# d150_zm1000_socket_rev_a.net
KiCad netlist of a schematic drawn in EAGLE
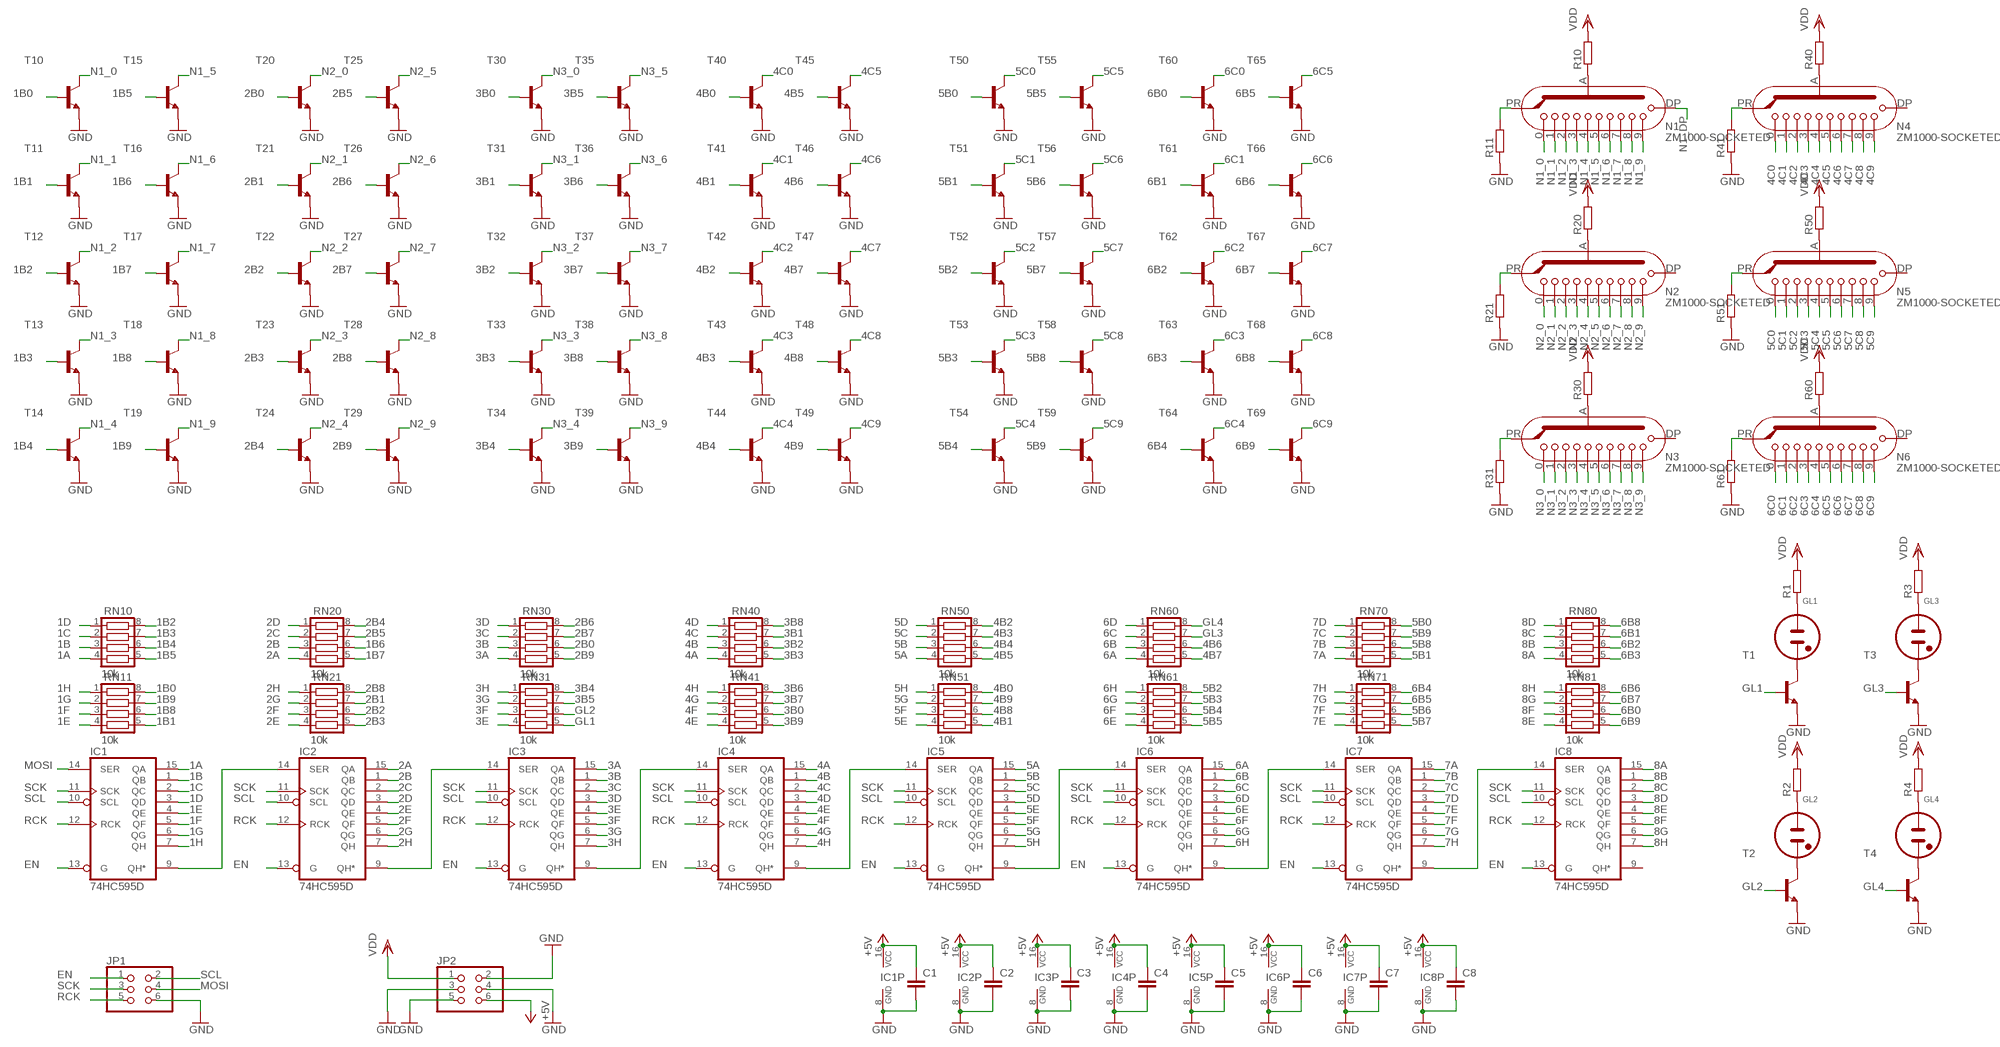
[diagram p0: schematic, sheet 1]

(export (version "E")
  (design (tool "Eeschema 10.0.6"))
  (components
    (comp (ref "C1")
      (value "C-EUC0603")
      (footprint "eagle-import:C0603")
      (libsource (lib "eagle-import") (part "C-EUC0603"))
    )
    (comp (ref "C2")
      (value "C-EUC0603")
      (footprint "eagle-import:C0603")
      (libsource (lib "eagle-import") (part "C-EUC0603"))
    )
    (comp (ref "C3")
      (value "C-EUC0603")
      (footprint "eagle-import:C0603")
      (libsource (lib "eagle-import") (part "C-EUC0603"))
    )
    (comp (ref "C4")
      (value "C-EUC0603")
      (footprint "eagle-import:C0603")
      (libsource (lib "eagle-import") (part "C-EUC0603"))
    )
    (comp (ref "C5")
      (value "C-EUC0603")
      (footprint "eagle-import:C0603")
      (libsource (lib "eagle-import") (part "C-EUC0603"))
    )
    (comp (ref "C6")
      (value "C-EUC0603")
      (footprint "eagle-import:C0603")
      (libsource (lib "eagle-import") (part "C-EUC0603"))
    )
    (comp (ref "C7")
      (value "C-EUC0603")
      (footprint "eagle-import:C0603")
      (libsource (lib "eagle-import") (part "C-EUC0603"))
    )
    (comp (ref "C8")
      (value "C-EUC0603")
      (footprint "eagle-import:C0603")
      (libsource (lib "eagle-import") (part "C-EUC0603"))
    )
    (comp (ref "GL1")
      (value "NE2-NEON-BULB-DRILL")
      (footprint "eagle-import:NE2-NEON-BULB-DRILL")
      (libsource (lib "eagle-import") (part "NE2-NEON-BULB-DRILL"))
    )
    (comp (ref "GL2")
      (value "NE2-NEON-BULB-DRILL")
      (footprint "eagle-import:NE2-NEON-BULB-DRILL")
      (libsource (lib "eagle-import") (part "NE2-NEON-BULB-DRILL"))
    )
    (comp (ref "GL3")
      (value "NE2-NEON-BULB-DRILL")
      (footprint "eagle-import:NE2-NEON-BULB-DRILL")
      (libsource (lib "eagle-import") (part "NE2-NEON-BULB-DRILL"))
    )
    (comp (ref "GL4")
      (value "NE2-NEON-BULB-DRILL")
      (footprint "eagle-import:NE2-NEON-BULB-DRILL")
      (libsource (lib "eagle-import") (part "NE2-NEON-BULB-DRILL"))
    )
    (comp (ref "IC1")
      (value "74HC595D")
      (footprint "eagle-import:SO16")
      (libsource (lib "eagle-import") (part "74595DHC"))
    )
    (comp (ref "IC2")
      (value "74HC595D")
      (footprint "eagle-import:SO16")
      (libsource (lib "eagle-import") (part "74595DHC"))
    )
    (comp (ref "IC3")
      (value "74HC595D")
      (footprint "eagle-import:SO16")
      (libsource (lib "eagle-import") (part "74595DHC"))
    )
    (comp (ref "IC4")
      (value "74HC595D")
      (footprint "eagle-import:SO16")
      (libsource (lib "eagle-import") (part "74595DHC"))
    )
    (comp (ref "IC5")
      (value "74HC595D")
      (footprint "eagle-import:SO16")
      (libsource (lib "eagle-import") (part "74595DHC"))
    )
    (comp (ref "IC6")
      (value "74HC595D")
      (footprint "eagle-import:SO16")
      (libsource (lib "eagle-import") (part "74595DHC"))
    )
    (comp (ref "IC7")
      (value "74HC595D")
      (footprint "eagle-import:SO16")
      (libsource (lib "eagle-import") (part "74595DHC"))
    )
    (comp (ref "IC8")
      (value "74HC595D")
      (footprint "eagle-import:SO16")
      (libsource (lib "eagle-import") (part "74595DHC"))
    )
    (comp (ref "JP1")
      (value "PINHD-2X3_2.54-SMD")
      (footprint "eagle-import:2X03SMD")
      (libsource (lib "eagle-import") (part "PINHD-2X3_2.54-SMD"))
    )
    (comp (ref "JP2")
      (value "PINHD-2X3_2.54-SMD")
      (footprint "eagle-import:2X03SMD")
      (libsource (lib "eagle-import") (part "PINHD-2X3_2.54-SMD"))
    )
    (comp (ref "N1")
      (value "ZM1000-SOCKETED")
      (footprint "eagle-import:ZM1000-SOCKETED")
      (libsource (lib "eagle-import") (part "ZM1000-SOCKETED"))
    )
    (comp (ref "N2")
      (value "ZM1000-SOCKETED")
      (footprint "eagle-import:ZM1000-SOCKETED")
      (libsource (lib "eagle-import") (part "ZM1000-SOCKETED"))
    )
    (comp (ref "N3")
      (value "ZM1000-SOCKETED")
      (footprint "eagle-import:ZM1000-SOCKETED")
      (libsource (lib "eagle-import") (part "ZM1000-SOCKETED"))
    )
    (comp (ref "N4")
      (value "ZM1000-SOCKETED")
      (footprint "eagle-import:ZM1000-SOCKETED")
      (libsource (lib "eagle-import") (part "ZM1000-SOCKETED"))
    )
    (comp (ref "N5")
      (value "ZM1000-SOCKETED")
      (footprint "eagle-import:ZM1000-SOCKETED")
      (libsource (lib "eagle-import") (part "ZM1000-SOCKETED"))
    )
    (comp (ref "N6")
      (value "ZM1000-SOCKETED")
      (footprint "eagle-import:ZM1000-SOCKETED")
      (libsource (lib "eagle-import") (part "ZM1000-SOCKETED"))
    )
    (comp (ref "R1")
      (value "R-EU_R0603")
      (footprint "eagle-import:R0603")
      (libsource (lib "eagle-import") (part "R-EU_R0603"))
    )
    (comp (ref "R2")
      (value "R-EU_R0603")
      (footprint "eagle-import:R0603")
      (libsource (lib "eagle-import") (part "R-EU_R0603"))
    )
    (comp (ref "R3")
      (value "R-EU_R0603")
      (footprint "eagle-import:R0603")
      (libsource (lib "eagle-import") (part "R-EU_R0603"))
    )
    (comp (ref "R4")
      (value "R-EU_R0603")
      (footprint "eagle-import:R0603")
      (libsource (lib "eagle-import") (part "R-EU_R0603"))
    )
    (comp (ref "R10")
      (value "R-EU_R0603")
      (footprint "eagle-import:R0603")
      (libsource (lib "eagle-import") (part "R-EU_R0603"))
    )
    (comp (ref "R11")
      (value "R-EU_R0603")
      (footprint "eagle-import:R0603")
      (libsource (lib "eagle-import") (part "R-EU_R0603"))
    )
    (comp (ref "R20")
      (value "R-EU_R0603")
      (footprint "eagle-import:R0603")
      (libsource (lib "eagle-import") (part "R-EU_R0603"))
    )
    (comp (ref "R21")
      (value "R-EU_R0603")
      (footprint "eagle-import:R0603")
      (libsource (lib "eagle-import") (part "R-EU_R0603"))
    )
    (comp (ref "R30")
      (value "R-EU_R0603")
      (footprint "eagle-import:R0603")
      (libsource (lib "eagle-import") (part "R-EU_R0603"))
    )
    (comp (ref "R31")
      (value "R-EU_R0603")
      (footprint "eagle-import:R0603")
      (libsource (lib "eagle-import") (part "R-EU_R0603"))
    )
    (comp (ref "R40")
      (value "R-EU_R0603")
      (footprint "eagle-import:R0603")
      (libsource (lib "eagle-import") (part "R-EU_R0603"))
    )
    (comp (ref "R41")
      (value "R-EU_R0603")
      (footprint "eagle-import:R0603")
      (libsource (lib "eagle-import") (part "R-EU_R0603"))
    )
    (comp (ref "R50")
      (value "R-EU_R0603")
      (footprint "eagle-import:R0603")
      (libsource (lib "eagle-import") (part "R-EU_R0603"))
    )
    (comp (ref "R51")
      (value "R-EU_R0603")
      (footprint "eagle-import:R0603")
      (libsource (lib "eagle-import") (part "R-EU_R0603"))
    )
    (comp (ref "R60")
      (value "R-EU_R0603")
      (footprint "eagle-import:R0603")
      (libsource (lib "eagle-import") (part "R-EU_R0603"))
    )
    (comp (ref "R61")
      (value "R-EU_R0603")
      (footprint "eagle-import:R0603")
      (libsource (lib "eagle-import") (part "R-EU_R0603"))
    )
    (comp (ref "RN10")
      (value "10k")
      (footprint "eagle-import:CTS742C083")
      (fields (field (name "OC_FARNELL") "unknown") (field (name "OC_NEWARK") "unknown"))
      (libsource (lib "eagle-import") (part "CTS742C083"))
    )
    (comp (ref "RN11")
      (value "10k")
      (footprint "eagle-import:CTS742C083")
      (fields (field (name "OC_FARNELL") "unknown") (field (name "OC_NEWARK") "unknown"))
      (libsource (lib "eagle-import") (part "CTS742C083"))
    )
    (comp (ref "RN20")
      (value "10k")
      (footprint "eagle-import:CTS742C083")
      (fields (field (name "OC_FARNELL") "unknown") (field (name "OC_NEWARK") "unknown"))
      (libsource (lib "eagle-import") (part "CTS742C083"))
    )
    (comp (ref "RN21")
      (value "10k")
      (footprint "eagle-import:CTS742C083")
      (fields (field (name "OC_FARNELL") "unknown") (field (name "OC_NEWARK") "unknown"))
      (libsource (lib "eagle-import") (part "CTS742C083"))
    )
    (comp (ref "RN30")
      (value "10k")
      (footprint "eagle-import:CTS742C083")
      (fields (field (name "OC_FARNELL") "unknown") (field (name "OC_NEWARK") "unknown"))
      (libsource (lib "eagle-import") (part "CTS742C083"))
    )
    (comp (ref "RN31")
      (value "10k")
      (footprint "eagle-import:CTS742C083")
      (fields (field (name "OC_FARNELL") "unknown") (field (name "OC_NEWARK") "unknown"))
      (libsource (lib "eagle-import") (part "CTS742C083"))
    )
    (comp (ref "RN40")
      (value "10k")
      (footprint "eagle-import:CTS742C083")
      (fields (field (name "OC_FARNELL") "unknown") (field (name "OC_NEWARK") "unknown"))
      (libsource (lib "eagle-import") (part "CTS742C083"))
    )
    (comp (ref "RN41")
      (value "10k")
      (footprint "eagle-import:CTS742C083")
      (fields (field (name "OC_FARNELL") "unknown") (field (name "OC_NEWARK") "unknown"))
      (libsource (lib "eagle-import") (part "CTS742C083"))
    )
    (comp (ref "RN50")
      (value "10k")
      (footprint "eagle-import:CTS742C083")
      (fields (field (name "OC_FARNELL") "unknown") (field (name "OC_NEWARK") "unknown"))
      (libsource (lib "eagle-import") (part "CTS742C083"))
    )
    (comp (ref "RN51")
      (value "10k")
      (footprint "eagle-import:CTS742C083")
      (fields (field (name "OC_FARNELL") "unknown") (field (name "OC_NEWARK") "unknown"))
      (libsource (lib "eagle-import") (part "CTS742C083"))
    )
    (comp (ref "RN60")
      (value "10k")
      (footprint "eagle-import:CTS742C083")
      (fields (field (name "OC_FARNELL") "unknown") (field (name "OC_NEWARK") "unknown"))
      (libsource (lib "eagle-import") (part "CTS742C083"))
    )
    (comp (ref "RN61")
      (value "10k")
      (footprint "eagle-import:CTS742C083")
      (fields (field (name "OC_FARNELL") "unknown") (field (name "OC_NEWARK") "unknown"))
      (libsource (lib "eagle-import") (part "CTS742C083"))
    )
    (comp (ref "RN70")
      (value "10k")
      (footprint "eagle-import:CTS742C083")
      (fields (field (name "OC_FARNELL") "unknown") (field (name "OC_NEWARK") "unknown"))
      (libsource (lib "eagle-import") (part "CTS742C083"))
    )
    (comp (ref "RN71")
      (value "10k")
      (footprint "eagle-import:CTS742C083")
      (fields (field (name "OC_FARNELL") "unknown") (field (name "OC_NEWARK") "unknown"))
      (libsource (lib "eagle-import") (part "CTS742C083"))
    )
    (comp (ref "RN80")
      (value "10k")
      (footprint "eagle-import:CTS742C083")
      (fields (field (name "OC_FARNELL") "unknown") (field (name "OC_NEWARK") "unknown"))
      (libsource (lib "eagle-import") (part "CTS742C083"))
    )
    (comp (ref "RN81")
      (value "10k")
      (footprint "eagle-import:CTS742C083")
      (fields (field (name "OC_FARNELL") "unknown") (field (name "OC_NEWARK") "unknown"))
      (libsource (lib "eagle-import") (part "CTS742C083"))
    )
    (comp (ref "T1")
      (value "SMBTA42")
      (footprint "eagle-import:SOT23")
      (libsource (lib "eagle-import") (part "SMBTA42"))
    )
    (comp (ref "T2")
      (value "SMBTA42")
      (footprint "eagle-import:SOT23")
      (libsource (lib "eagle-import") (part "SMBTA42"))
    )
    (comp (ref "T3")
      (value "SMBTA42")
      (footprint "eagle-import:SOT23")
      (libsource (lib "eagle-import") (part "SMBTA42"))
    )
    (comp (ref "T4")
      (value "SMBTA42")
      (footprint "eagle-import:SOT23")
      (libsource (lib "eagle-import") (part "SMBTA42"))
    )
    (comp (ref "T10")
      (value "SMBTA42")
      (footprint "eagle-import:SOT23")
      (libsource (lib "eagle-import") (part "SMBTA42"))
    )
    (comp (ref "T11")
      (value "SMBTA42")
      (footprint "eagle-import:SOT23")
      (libsource (lib "eagle-import") (part "SMBTA42"))
    )
    (comp (ref "T12")
      (value "SMBTA42")
      (footprint "eagle-import:SOT23")
      (libsource (lib "eagle-import") (part "SMBTA42"))
    )
    (comp (ref "T13")
      (value "SMBTA42")
      (footprint "eagle-import:SOT23")
      (libsource (lib "eagle-import") (part "SMBTA42"))
    )
    (comp (ref "T14")
      (value "SMBTA42")
      (footprint "eagle-import:SOT23")
      (libsource (lib "eagle-import") (part "SMBTA42"))
    )
    (comp (ref "T15")
      (value "SMBTA42")
      (footprint "eagle-import:SOT23")
      (libsource (lib "eagle-import") (part "SMBTA42"))
    )
    (comp (ref "T16")
      (value "SMBTA42")
      (footprint "eagle-import:SOT23")
      (libsource (lib "eagle-import") (part "SMBTA42"))
    )
    (comp (ref "T17")
      (value "SMBTA42")
      (footprint "eagle-import:SOT23")
      (libsource (lib "eagle-import") (part "SMBTA42"))
    )
    (comp (ref "T18")
      (value "SMBTA42")
      (footprint "eagle-import:SOT23")
      (libsource (lib "eagle-import") (part "SMBTA42"))
    )
    (comp (ref "T19")
      (value "SMBTA42")
      (footprint "eagle-import:SOT23")
      (libsource (lib "eagle-import") (part "SMBTA42"))
    )
    (comp (ref "T20")
      (value "SMBTA42")
      (footprint "eagle-import:SOT23")
      (libsource (lib "eagle-import") (part "SMBTA42"))
    )
    (comp (ref "T21")
      (value "SMBTA42")
      (footprint "eagle-import:SOT23")
      (libsource (lib "eagle-import") (part "SMBTA42"))
    )
    (comp (ref "T22")
      (value "SMBTA42")
      (footprint "eagle-import:SOT23")
      (libsource (lib "eagle-import") (part "SMBTA42"))
    )
    (comp (ref "T23")
      (value "SMBTA42")
      (footprint "eagle-import:SOT23")
      (libsource (lib "eagle-import") (part "SMBTA42"))
    )
    (comp (ref "T24")
      (value "SMBTA42")
      (footprint "eagle-import:SOT23")
      (libsource (lib "eagle-import") (part "SMBTA42"))
    )
    (comp (ref "T25")
      (value "SMBTA42")
      (footprint "eagle-import:SOT23")
      (libsource (lib "eagle-import") (part "SMBTA42"))
    )
    (comp (ref "T26")
      (value "SMBTA42")
      (footprint "eagle-import:SOT23")
      (libsource (lib "eagle-import") (part "SMBTA42"))
    )
    (comp (ref "T27")
      (value "SMBTA42")
      (footprint "eagle-import:SOT23")
      (libsource (lib "eagle-import") (part "SMBTA42"))
    )
    (comp (ref "T28")
      (value "SMBTA42")
      (footprint "eagle-import:SOT23")
      (libsource (lib "eagle-import") (part "SMBTA42"))
    )
    (comp (ref "T29")
      (value "SMBTA42")
      (footprint "eagle-import:SOT23")
      (libsource (lib "eagle-import") (part "SMBTA42"))
    )
    (comp (ref "T30")
      (value "SMBTA42")
      (footprint "eagle-import:SOT23")
      (libsource (lib "eagle-import") (part "SMBTA42"))
    )
    (comp (ref "T31")
      (value "SMBTA42")
      (footprint "eagle-import:SOT23")
      (libsource (lib "eagle-import") (part "SMBTA42"))
    )
    (comp (ref "T32")
      (value "SMBTA42")
      (footprint "eagle-import:SOT23")
      (libsource (lib "eagle-import") (part "SMBTA42"))
    )
    (comp (ref "T33")
      (value "SMBTA42")
      (footprint "eagle-import:SOT23")
      (libsource (lib "eagle-import") (part "SMBTA42"))
    )
    (comp (ref "T34")
      (value "SMBTA42")
      (footprint "eagle-import:SOT23")
      (libsource (lib "eagle-import") (part "SMBTA42"))
    )
    (comp (ref "T35")
      (value "SMBTA42")
      (footprint "eagle-import:SOT23")
      (libsource (lib "eagle-import") (part "SMBTA42"))
    )
    (comp (ref "T36")
      (value "SMBTA42")
      (footprint "eagle-import:SOT23")
      (libsource (lib "eagle-import") (part "SMBTA42"))
    )
    (comp (ref "T37")
      (value "SMBTA42")
      (footprint "eagle-import:SOT23")
      (libsource (lib "eagle-import") (part "SMBTA42"))
    )
    (comp (ref "T38")
      (value "SMBTA42")
      (footprint "eagle-import:SOT23")
      (libsource (lib "eagle-import") (part "SMBTA42"))
    )
    (comp (ref "T39")
      (value "SMBTA42")
      (footprint "eagle-import:SOT23")
      (libsource (lib "eagle-import") (part "SMBTA42"))
    )
    (comp (ref "T40")
      (value "SMBTA42")
      (footprint "eagle-import:SOT23")
      (libsource (lib "eagle-import") (part "SMBTA42"))
    )
    (comp (ref "T41")
      (value "SMBTA42")
      (footprint "eagle-import:SOT23")
      (libsource (lib "eagle-import") (part "SMBTA42"))
    )
    (comp (ref "T42")
      (value "SMBTA42")
      (footprint "eagle-import:SOT23")
      (libsource (lib "eagle-import") (part "SMBTA42"))
    )
    (comp (ref "T43")
      (value "SMBTA42")
      (footprint "eagle-import:SOT23")
      (libsource (lib "eagle-import") (part "SMBTA42"))
    )
    (comp (ref "T44")
      (value "SMBTA42")
      (footprint "eagle-import:SOT23")
      (libsource (lib "eagle-import") (part "SMBTA42"))
    )
    (comp (ref "T45")
      (value "SMBTA42")
      (footprint "eagle-import:SOT23")
      (libsource (lib "eagle-import") (part "SMBTA42"))
    )
    (comp (ref "T46")
      (value "SMBTA42")
      (footprint "eagle-import:SOT23")
      (libsource (lib "eagle-import") (part "SMBTA42"))
    )
    (comp (ref "T47")
      (value "SMBTA42")
      (footprint "eagle-import:SOT23")
      (libsource (lib "eagle-import") (part "SMBTA42"))
    )
    (comp (ref "T48")
      (value "SMBTA42")
      (footprint "eagle-import:SOT23")
      (libsource (lib "eagle-import") (part "SMBTA42"))
    )
    (comp (ref "T49")
      (value "SMBTA42")
      (footprint "eagle-import:SOT23")
      (libsource (lib "eagle-import") (part "SMBTA42"))
    )
    (comp (ref "T50")
      (value "SMBTA42")
      (footprint "eagle-import:SOT23")
      (libsource (lib "eagle-import") (part "SMBTA42"))
    )
    (comp (ref "T51")
      (value "SMBTA42")
      (footprint "eagle-import:SOT23")
      (libsource (lib "eagle-import") (part "SMBTA42"))
    )
    (comp (ref "T52")
      (value "SMBTA42")
      (footprint "eagle-import:SOT23")
      (libsource (lib "eagle-import") (part "SMBTA42"))
    )
    (comp (ref "T53")
      (value "SMBTA42")
      (footprint "eagle-import:SOT23")
      (libsource (lib "eagle-import") (part "SMBTA42"))
    )
    (comp (ref "T54")
      (value "SMBTA42")
      (footprint "eagle-import:SOT23")
      (libsource (lib "eagle-import") (part "SMBTA42"))
    )
    (comp (ref "T55")
      (value "SMBTA42")
      (footprint "eagle-import:SOT23")
      (libsource (lib "eagle-import") (part "SMBTA42"))
    )
    (comp (ref "T56")
      (value "SMBTA42")
      (footprint "eagle-import:SOT23")
      (libsource (lib "eagle-import") (part "SMBTA42"))
    )
    (comp (ref "T57")
      (value "SMBTA42")
      (footprint "eagle-import:SOT23")
      (libsource (lib "eagle-import") (part "SMBTA42"))
    )
    (comp (ref "T58")
      (value "SMBTA42")
      (footprint "eagle-import:SOT23")
      (libsource (lib "eagle-import") (part "SMBTA42"))
    )
    (comp (ref "T59")
      (value "SMBTA42")
      (footprint "eagle-import:SOT23")
      (libsource (lib "eagle-import") (part "SMBTA42"))
    )
    (comp (ref "T60")
      (value "SMBTA42")
      (footprint "eagle-import:SOT23")
      (libsource (lib "eagle-import") (part "SMBTA42"))
    )
    (comp (ref "T61")
      (value "SMBTA42")
      (footprint "eagle-import:SOT23")
      (libsource (lib "eagle-import") (part "SMBTA42"))
    )
    (comp (ref "T62")
      (value "SMBTA42")
      (footprint "eagle-import:SOT23")
      (libsource (lib "eagle-import") (part "SMBTA42"))
    )
    (comp (ref "T63")
      (value "SMBTA42")
      (footprint "eagle-import:SOT23")
      (libsource (lib "eagle-import") (part "SMBTA42"))
    )
    (comp (ref "T64")
      (value "SMBTA42")
      (footprint "eagle-import:SOT23")
      (libsource (lib "eagle-import") (part "SMBTA42"))
    )
    (comp (ref "T65")
      (value "SMBTA42")
      (footprint "eagle-import:SOT23")
      (libsource (lib "eagle-import") (part "SMBTA42"))
    )
    (comp (ref "T66")
      (value "SMBTA42")
      (footprint "eagle-import:SOT23")
      (libsource (lib "eagle-import") (part "SMBTA42"))
    )
    (comp (ref "T67")
      (value "SMBTA42")
      (footprint "eagle-import:SOT23")
      (libsource (lib "eagle-import") (part "SMBTA42"))
    )
    (comp (ref "T68")
      (value "SMBTA42")
      (footprint "eagle-import:SOT23")
      (libsource (lib "eagle-import") (part "SMBTA42"))
    )
    (comp (ref "T69")
      (value "SMBTA42")
      (footprint "eagle-import:SOT23")
      (libsource (lib "eagle-import") (part "SMBTA42"))
    )
  )
  (nets
    (net (code "1") (name "+5V") (class "Default")
      (node (ref "C1") (pin "1") (pinfunction "1_1") (pintype "passive"))
      (node (ref "C2") (pin "1") (pinfunction "1_1") (pintype "passive"))
      (node (ref "C3") (pin "1") (pinfunction "1_1") (pintype "passive"))
      (node (ref "C4") (pin "1") (pinfunction "1_1") (pintype "passive"))
      (node (ref "C5") (pin "1") (pinfunction "1_1") (pintype "passive"))
      (node (ref "C6") (pin "1") (pinfunction "1_1") (pintype "passive"))
      (node (ref "C7") (pin "1") (pinfunction "1_1") (pintype "passive"))
      (node (ref "C8") (pin "1") (pinfunction "1_1") (pintype "passive"))
      (node (ref "IC1") (pin "16") (pinfunction "VCC_16") (pintype "power_in"))
      (node (ref "IC2") (pin "16") (pinfunction "VCC_16") (pintype "power_in"))
      (node (ref "IC3") (pin "16") (pinfunction "VCC_16") (pintype "power_in"))
      (node (ref "IC4") (pin "16") (pinfunction "VCC_16") (pintype "power_in"))
      (node (ref "IC5") (pin "16") (pinfunction "VCC_16") (pintype "power_in"))
      (node (ref "IC6") (pin "16") (pinfunction "VCC_16") (pintype "power_in"))
      (node (ref "IC7") (pin "16") (pinfunction "VCC_16") (pintype "power_in"))
      (node (ref "IC8") (pin "16") (pinfunction "VCC_16") (pintype "power_in"))
      (node (ref "JP2") (pin "6") (pinfunction "6_6") (pintype "passive"))
    )
    (net (code "2") (name "/1A") (class "Default")
      (node (ref "IC1") (pin "15") (pinfunction "QA_15") (pintype "tri_state"))
      (node (ref "RN10") (pin "4") (pinfunction "4_4") (pintype "passive"))
    )
    (net (code "3") (name "/1B") (class "Default")
      (node (ref "IC1") (pin "1") (pinfunction "QB_1") (pintype "tri_state"))
      (node (ref "RN10") (pin "3") (pinfunction "3_3") (pintype "passive"))
    )
    (net (code "4") (name "/1B0") (class "Default")
      (node (ref "RN11") (pin "8") (pinfunction "8_8") (pintype "passive"))
      (node (ref "T10") (pin "1") (pinfunction "B_1") (pintype "passive"))
    )
    (net (code "5") (name "/1B1") (class "Default")
      (node (ref "RN11") (pin "5") (pinfunction "5_5") (pintype "passive"))
      (node (ref "T11") (pin "1") (pinfunction "B_1") (pintype "passive"))
    )
    (net (code "6") (name "/1B2") (class "Default")
      (node (ref "RN10") (pin "8") (pinfunction "8_8") (pintype "passive"))
      (node (ref "T12") (pin "1") (pinfunction "B_1") (pintype "passive"))
    )
    (net (code "7") (name "/1B3") (class "Default")
      (node (ref "RN10") (pin "7") (pinfunction "7_7") (pintype "passive"))
      (node (ref "T13") (pin "1") (pinfunction "B_1") (pintype "passive"))
    )
    (net (code "8") (name "/1B4") (class "Default")
      (node (ref "RN10") (pin "6") (pinfunction "6_6") (pintype "passive"))
      (node (ref "T14") (pin "1") (pinfunction "B_1") (pintype "passive"))
    )
    (net (code "9") (name "/1B5") (class "Default")
      (node (ref "RN10") (pin "5") (pinfunction "5_5") (pintype "passive"))
      (node (ref "T15") (pin "1") (pinfunction "B_1") (pintype "passive"))
    )
    (net (code "10") (name "/1B6") (class "Default")
      (node (ref "RN20") (pin "6") (pinfunction "6_6") (pintype "passive"))
      (node (ref "T16") (pin "1") (pinfunction "B_1") (pintype "passive"))
    )
    (net (code "11") (name "/1B7") (class "Default")
      (node (ref "RN20") (pin "5") (pinfunction "5_5") (pintype "passive"))
      (node (ref "T17") (pin "1") (pinfunction "B_1") (pintype "passive"))
    )
    (net (code "12") (name "/1B8") (class "Default")
      (node (ref "RN11") (pin "6") (pinfunction "6_6") (pintype "passive"))
      (node (ref "T18") (pin "1") (pinfunction "B_1") (pintype "passive"))
    )
    (net (code "13") (name "/1B9") (class "Default")
      (node (ref "RN11") (pin "7") (pinfunction "7_7") (pintype "passive"))
      (node (ref "T19") (pin "1") (pinfunction "B_1") (pintype "passive"))
    )
    (net (code "14") (name "/1C") (class "Default")
      (node (ref "IC1") (pin "2") (pinfunction "QC_2") (pintype "tri_state"))
      (node (ref "RN10") (pin "2") (pinfunction "2_2") (pintype "passive"))
    )
    (net (code "15") (name "/1D") (class "Default")
      (node (ref "IC1") (pin "3") (pinfunction "QD_3") (pintype "tri_state"))
      (node (ref "RN10") (pin "1") (pinfunction "1_1") (pintype "passive"))
    )
    (net (code "16") (name "/1E") (class "Default")
      (node (ref "IC1") (pin "4") (pinfunction "QE_4") (pintype "tri_state"))
      (node (ref "RN11") (pin "4") (pinfunction "4_4") (pintype "passive"))
    )
    (net (code "17") (name "/1F") (class "Default")
      (node (ref "IC1") (pin "5") (pinfunction "QF_5") (pintype "tri_state"))
      (node (ref "RN11") (pin "3") (pinfunction "3_3") (pintype "passive"))
    )
    (net (code "18") (name "/1G") (class "Default")
      (node (ref "IC1") (pin "6") (pinfunction "QG_6") (pintype "tri_state"))
      (node (ref "RN11") (pin "2") (pinfunction "2_2") (pintype "passive"))
    )
    (net (code "19") (name "/1H") (class "Default")
      (node (ref "IC1") (pin "7") (pinfunction "QH_7") (pintype "tri_state"))
      (node (ref "RN11") (pin "1") (pinfunction "1_1") (pintype "passive"))
    )
    (net (code "20") (name "/2A") (class "Default")
      (node (ref "IC2") (pin "15") (pinfunction "QA_15") (pintype "tri_state"))
      (node (ref "RN20") (pin "4") (pinfunction "4_4") (pintype "passive"))
    )
    (net (code "21") (name "/2B") (class "Default")
      (node (ref "IC2") (pin "1") (pinfunction "QB_1") (pintype "tri_state"))
      (node (ref "RN20") (pin "3") (pinfunction "3_3") (pintype "passive"))
    )
    (net (code "22") (name "/2B0") (class "Default")
      (node (ref "RN30") (pin "6") (pinfunction "6_6") (pintype "passive"))
      (node (ref "T20") (pin "1") (pinfunction "B_1") (pintype "passive"))
    )
    (net (code "23") (name "/2B1") (class "Default")
      (node (ref "RN21") (pin "7") (pinfunction "7_7") (pintype "passive"))
      (node (ref "T21") (pin "1") (pinfunction "B_1") (pintype "passive"))
    )
    (net (code "24") (name "/2B2") (class "Default")
      (node (ref "RN21") (pin "6") (pinfunction "6_6") (pintype "passive"))
      (node (ref "T22") (pin "1") (pinfunction "B_1") (pintype "passive"))
    )
    (net (code "25") (name "/2B3") (class "Default")
      (node (ref "RN21") (pin "5") (pinfunction "5_5") (pintype "passive"))
      (node (ref "T23") (pin "1") (pinfunction "B_1") (pintype "passive"))
    )
    (net (code "26") (name "/2B4") (class "Default")
      (node (ref "RN20") (pin "8") (pinfunction "8_8") (pintype "passive"))
      (node (ref "T24") (pin "1") (pinfunction "B_1") (pintype "passive"))
    )
    (net (code "27") (name "/2B5") (class "Default")
      (node (ref "RN20") (pin "7") (pinfunction "7_7") (pintype "passive"))
      (node (ref "T25") (pin "1") (pinfunction "B_1") (pintype "passive"))
    )
    (net (code "28") (name "/2B6") (class "Default")
      (node (ref "RN30") (pin "8") (pinfunction "8_8") (pintype "passive"))
      (node (ref "T26") (pin "1") (pinfunction "B_1") (pintype "passive"))
    )
    (net (code "29") (name "/2B7") (class "Default")
      (node (ref "RN30") (pin "7") (pinfunction "7_7") (pintype "passive"))
      (node (ref "T27") (pin "1") (pinfunction "B_1") (pintype "passive"))
    )
    (net (code "30") (name "/2B8") (class "Default")
      (node (ref "RN21") (pin "8") (pinfunction "8_8") (pintype "passive"))
      (node (ref "T28") (pin "1") (pinfunction "B_1") (pintype "passive"))
    )
    (net (code "31") (name "/2B9") (class "Default")
      (node (ref "RN30") (pin "5") (pinfunction "5_5") (pintype "passive"))
      (node (ref "T29") (pin "1") (pinfunction "B_1") (pintype "passive"))
    )
    (net (code "32") (name "/2C") (class "Default")
      (node (ref "IC2") (pin "2") (pinfunction "QC_2") (pintype "tri_state"))
      (node (ref "RN20") (pin "2") (pinfunction "2_2") (pintype "passive"))
    )
    (net (code "33") (name "/2D") (class "Default")
      (node (ref "IC2") (pin "3") (pinfunction "QD_3") (pintype "tri_state"))
      (node (ref "RN20") (pin "1") (pinfunction "1_1") (pintype "passive"))
    )
    (net (code "34") (name "/2E") (class "Default")
      (node (ref "IC2") (pin "4") (pinfunction "QE_4") (pintype "tri_state"))
      (node (ref "RN21") (pin "4") (pinfunction "4_4") (pintype "passive"))
    )
    (net (code "35") (name "/2F") (class "Default")
      (node (ref "IC2") (pin "5") (pinfunction "QF_5") (pintype "tri_state"))
      (node (ref "RN21") (pin "3") (pinfunction "3_3") (pintype "passive"))
    )
    (net (code "36") (name "/2G") (class "Default")
      (node (ref "IC2") (pin "6") (pinfunction "QG_6") (pintype "tri_state"))
      (node (ref "RN21") (pin "2") (pinfunction "2_2") (pintype "passive"))
    )
    (net (code "37") (name "/2H") (class "Default")
      (node (ref "IC2") (pin "7") (pinfunction "QH_7") (pintype "tri_state"))
      (node (ref "RN21") (pin "1") (pinfunction "1_1") (pintype "passive"))
    )
    (net (code "38") (name "/3A") (class "Default")
      (node (ref "IC3") (pin "15") (pinfunction "QA_15") (pintype "tri_state"))
      (node (ref "RN30") (pin "4") (pinfunction "4_4") (pintype "passive"))
    )
    (net (code "39") (name "/3B") (class "Default")
      (node (ref "IC3") (pin "1") (pinfunction "QB_1") (pintype "tri_state"))
      (node (ref "RN30") (pin "3") (pinfunction "3_3") (pintype "passive"))
    )
    (net (code "40") (name "/3B0") (class "Default")
      (node (ref "RN41") (pin "6") (pinfunction "6_6") (pintype "passive"))
      (node (ref "T30") (pin "1") (pinfunction "B_1") (pintype "passive"))
    )
    (net (code "41") (name "/3B1") (class "Default")
      (node (ref "RN40") (pin "7") (pinfunction "7_7") (pintype "passive"))
      (node (ref "T31") (pin "1") (pinfunction "B_1") (pintype "passive"))
    )
    (net (code "42") (name "/3B2") (class "Default")
      (node (ref "RN40") (pin "6") (pinfunction "6_6") (pintype "passive"))
      (node (ref "T32") (pin "1") (pinfunction "B_1") (pintype "passive"))
    )
    (net (code "43") (name "/3B3") (class "Default")
      (node (ref "RN40") (pin "5") (pinfunction "5_5") (pintype "passive"))
      (node (ref "T33") (pin "1") (pinfunction "B_1") (pintype "passive"))
    )
    (net (code "44") (name "/3B4") (class "Default")
      (node (ref "RN31") (pin "8") (pinfunction "8_8") (pintype "passive"))
      (node (ref "T34") (pin "1") (pinfunction "B_1") (pintype "passive"))
    )
    (net (code "45") (name "/3B5") (class "Default")
      (node (ref "RN31") (pin "7") (pinfunction "7_7") (pintype "passive"))
      (node (ref "T35") (pin "1") (pinfunction "B_1") (pintype "passive"))
    )
    (net (code "46") (name "/3B6") (class "Default")
      (node (ref "RN41") (pin "8") (pinfunction "8_8") (pintype "passive"))
      (node (ref "T36") (pin "1") (pinfunction "B_1") (pintype "passive"))
    )
    (net (code "47") (name "/3B7") (class "Default")
      (node (ref "RN41") (pin "7") (pinfunction "7_7") (pintype "passive"))
      (node (ref "T37") (pin "1") (pinfunction "B_1") (pintype "passive"))
    )
    (net (code "48") (name "/3B8") (class "Default")
      (node (ref "RN40") (pin "8") (pinfunction "8_8") (pintype "passive"))
      (node (ref "T38") (pin "1") (pinfunction "B_1") (pintype "passive"))
    )
    (net (code "49") (name "/3B9") (class "Default")
      (node (ref "RN41") (pin "5") (pinfunction "5_5") (pintype "passive"))
      (node (ref "T39") (pin "1") (pinfunction "B_1") (pintype "passive"))
    )
    (net (code "50") (name "/3C") (class "Default")
      (node (ref "IC3") (pin "2") (pinfunction "QC_2") (pintype "tri_state"))
      (node (ref "RN30") (pin "2") (pinfunction "2_2") (pintype "passive"))
    )
    (net (code "51") (name "/3D") (class "Default")
      (node (ref "IC3") (pin "3") (pinfunction "QD_3") (pintype "tri_state"))
      (node (ref "RN30") (pin "1") (pinfunction "1_1") (pintype "passive"))
    )
    (net (code "52") (name "/3E") (class "Default")
      (node (ref "IC3") (pin "4") (pinfunction "QE_4") (pintype "tri_state"))
      (node (ref "RN31") (pin "4") (pinfunction "4_4") (pintype "passive"))
    )
    (net (code "53") (name "/3F") (class "Default")
      (node (ref "IC3") (pin "5") (pinfunction "QF_5") (pintype "tri_state"))
      (node (ref "RN31") (pin "3") (pinfunction "3_3") (pintype "passive"))
    )
    (net (code "54") (name "/3G") (class "Default")
      (node (ref "IC3") (pin "6") (pinfunction "QG_6") (pintype "tri_state"))
      (node (ref "RN31") (pin "2") (pinfunction "2_2") (pintype "passive"))
    )
    (net (code "55") (name "/3H") (class "Default")
      (node (ref "IC3") (pin "7") (pinfunction "QH_7") (pintype "tri_state"))
      (node (ref "RN31") (pin "1") (pinfunction "1_1") (pintype "passive"))
    )
    (net (code "56") (name "/4A") (class "Default")
      (node (ref "IC4") (pin "15") (pinfunction "QA_15") (pintype "tri_state"))
      (node (ref "RN40") (pin "4") (pinfunction "4_4") (pintype "passive"))
    )
    (net (code "57") (name "/4B") (class "Default")
      (node (ref "IC4") (pin "1") (pinfunction "QB_1") (pintype "tri_state"))
      (node (ref "RN40") (pin "3") (pinfunction "3_3") (pintype "passive"))
    )
    (net (code "58") (name "/4B0") (class "Default")
      (node (ref "RN51") (pin "8") (pinfunction "8_8") (pintype "passive"))
      (node (ref "T40") (pin "1") (pinfunction "B_1") (pintype "passive"))
    )
    (net (code "59") (name "/4B1") (class "Default")
      (node (ref "RN51") (pin "5") (pinfunction "5_5") (pintype "passive"))
      (node (ref "T41") (pin "1") (pinfunction "B_1") (pintype "passive"))
    )
    (net (code "60") (name "/4B2") (class "Default")
      (node (ref "RN50") (pin "8") (pinfunction "8_8") (pintype "passive"))
      (node (ref "T42") (pin "1") (pinfunction "B_1") (pintype "passive"))
    )
    (net (code "61") (name "/4B3") (class "Default")
      (node (ref "RN50") (pin "7") (pinfunction "7_7") (pintype "passive"))
      (node (ref "T43") (pin "1") (pinfunction "B_1") (pintype "passive"))
    )
    (net (code "62") (name "/4B4") (class "Default")
      (node (ref "RN50") (pin "6") (pinfunction "6_6") (pintype "passive"))
      (node (ref "T44") (pin "1") (pinfunction "B_1") (pintype "passive"))
    )
    (net (code "63") (name "/4B5") (class "Default")
      (node (ref "RN50") (pin "5") (pinfunction "5_5") (pintype "passive"))
      (node (ref "T45") (pin "1") (pinfunction "B_1") (pintype "passive"))
    )
    (net (code "64") (name "/4B6") (class "Default")
      (node (ref "RN60") (pin "6") (pinfunction "6_6") (pintype "passive"))
      (node (ref "T46") (pin "1") (pinfunction "B_1") (pintype "passive"))
    )
    (net (code "65") (name "/4B7") (class "Default")
      (node (ref "RN60") (pin "5") (pinfunction "5_5") (pintype "passive"))
      (node (ref "T47") (pin "1") (pinfunction "B_1") (pintype "passive"))
    )
    (net (code "66") (name "/4B8") (class "Default")
      (node (ref "RN51") (pin "6") (pinfunction "6_6") (pintype "passive"))
      (node (ref "T48") (pin "1") (pinfunction "B_1") (pintype "passive"))
    )
    (net (code "67") (name "/4B9") (class "Default")
      (node (ref "RN51") (pin "7") (pinfunction "7_7") (pintype "passive"))
      (node (ref "T49") (pin "1") (pinfunction "B_1") (pintype "passive"))
    )
    (net (code "68") (name "/4C") (class "Default")
      (node (ref "IC4") (pin "2") (pinfunction "QC_2") (pintype "tri_state"))
      (node (ref "RN40") (pin "2") (pinfunction "2_2") (pintype "passive"))
    )
    (net (code "69") (name "/4C0") (class "Default")
      (node (ref "N4") (pin "K0") (pinfunction "0_K0") (pintype "bidirectional"))
      (node (ref "T40") (pin "3") (pinfunction "C_3") (pintype "passive"))
    )
    (net (code "70") (name "/4C1") (class "Default")
      (node (ref "N4") (pin "K1") (pinfunction "1_K1") (pintype "bidirectional"))
      (node (ref "T41") (pin "3") (pinfunction "C_3") (pintype "passive"))
    )
    (net (code "71") (name "/4C2") (class "Default")
      (node (ref "N4") (pin "K2") (pinfunction "2_K2") (pintype "bidirectional"))
      (node (ref "T42") (pin "3") (pinfunction "C_3") (pintype "passive"))
    )
    (net (code "72") (name "/4C3") (class "Default")
      (node (ref "N4") (pin "K3") (pinfunction "3_K3") (pintype "bidirectional"))
      (node (ref "T43") (pin "3") (pinfunction "C_3") (pintype "passive"))
    )
    (net (code "73") (name "/4C4") (class "Default")
      (node (ref "N4") (pin "K4") (pinfunction "4_K4") (pintype "bidirectional"))
      (node (ref "T44") (pin "3") (pinfunction "C_3") (pintype "passive"))
    )
    (net (code "74") (name "/4C5") (class "Default")
      (node (ref "N4") (pin "K5") (pinfunction "5_K5") (pintype "bidirectional"))
      (node (ref "T45") (pin "3") (pinfunction "C_3") (pintype "passive"))
    )
    (net (code "75") (name "/4C6") (class "Default")
      (node (ref "N4") (pin "K6") (pinfunction "6_K6") (pintype "bidirectional"))
      (node (ref "T46") (pin "3") (pinfunction "C_3") (pintype "passive"))
    )
    (net (code "76") (name "/4C7") (class "Default")
      (node (ref "N4") (pin "K7") (pinfunction "7_K7") (pintype "bidirectional"))
      (node (ref "T47") (pin "3") (pinfunction "C_3") (pintype "passive"))
    )
    (net (code "77") (name "/4C8") (class "Default")
      (node (ref "N4") (pin "K8") (pinfunction "8_K8") (pintype "bidirectional"))
      (node (ref "T48") (pin "3") (pinfunction "C_3") (pintype "passive"))
    )
    (net (code "78") (name "/4C9") (class "Default")
      (node (ref "N4") (pin "K9") (pinfunction "9_K9") (pintype "bidirectional"))
      (node (ref "T49") (pin "3") (pinfunction "C_3") (pintype "passive"))
    )
    (net (code "79") (name "/4D") (class "Default")
      (node (ref "IC4") (pin "3") (pinfunction "QD_3") (pintype "tri_state"))
      (node (ref "RN40") (pin "1") (pinfunction "1_1") (pintype "passive"))
    )
    (net (code "80") (name "/4E") (class "Default")
      (node (ref "IC4") (pin "4") (pinfunction "QE_4") (pintype "tri_state"))
      (node (ref "RN41") (pin "4") (pinfunction "4_4") (pintype "passive"))
    )
    (net (code "81") (name "/4F") (class "Default")
      (node (ref "IC4") (pin "5") (pinfunction "QF_5") (pintype "tri_state"))
      (node (ref "RN41") (pin "3") (pinfunction "3_3") (pintype "passive"))
    )
    (net (code "82") (name "/4G") (class "Default")
      (node (ref "IC4") (pin "6") (pinfunction "QG_6") (pintype "tri_state"))
      (node (ref "RN41") (pin "2") (pinfunction "2_2") (pintype "passive"))
    )
    (net (code "83") (name "/4H") (class "Default")
      (node (ref "IC4") (pin "7") (pinfunction "QH_7") (pintype "tri_state"))
      (node (ref "RN41") (pin "1") (pinfunction "1_1") (pintype "passive"))
    )
    (net (code "84") (name "/5A") (class "Default")
      (node (ref "IC5") (pin "15") (pinfunction "QA_15") (pintype "tri_state"))
      (node (ref "RN50") (pin "4") (pinfunction "4_4") (pintype "passive"))
    )
    (net (code "85") (name "/5B") (class "Default")
      (node (ref "IC5") (pin "1") (pinfunction "QB_1") (pintype "tri_state"))
      (node (ref "RN50") (pin "3") (pinfunction "3_3") (pintype "passive"))
    )
    (net (code "86") (name "/5B0") (class "Default")
      (node (ref "RN70") (pin "8") (pinfunction "8_8") (pintype "passive"))
      (node (ref "T50") (pin "1") (pinfunction "B_1") (pintype "passive"))
    )
    (net (code "87") (name "/5B1") (class "Default")
      (node (ref "RN70") (pin "5") (pinfunction "5_5") (pintype "passive"))
      (node (ref "T51") (pin "1") (pinfunction "B_1") (pintype "passive"))
    )
    (net (code "88") (name "/5B2") (class "Default")
      (node (ref "RN61") (pin "8") (pinfunction "8_8") (pintype "passive"))
      (node (ref "T52") (pin "1") (pinfunction "B_1") (pintype "passive"))
    )
    (net (code "89") (name "/5B3") (class "Default")
      (node (ref "RN61") (pin "7") (pinfunction "7_7") (pintype "passive"))
      (node (ref "T53") (pin "1") (pinfunction "B_1") (pintype "passive"))
    )
    (net (code "90") (name "/5B4") (class "Default")
      (node (ref "RN61") (pin "6") (pinfunction "6_6") (pintype "passive"))
      (node (ref "T54") (pin "1") (pinfunction "B_1") (pintype "passive"))
    )
    (net (code "91") (name "/5B5") (class "Default")
      (node (ref "RN61") (pin "5") (pinfunction "5_5") (pintype "passive"))
      (node (ref "T55") (pin "1") (pinfunction "B_1") (pintype "passive"))
    )
    (net (code "92") (name "/5B6") (class "Default")
      (node (ref "RN71") (pin "6") (pinfunction "6_6") (pintype "passive"))
      (node (ref "T56") (pin "1") (pinfunction "B_1") (pintype "passive"))
    )
    (net (code "93") (name "/5B7") (class "Default")
      (node (ref "RN71") (pin "5") (pinfunction "5_5") (pintype "passive"))
      (node (ref "T57") (pin "1") (pinfunction "B_1") (pintype "passive"))
    )
    (net (code "94") (name "/5B8") (class "Default")
      (node (ref "RN70") (pin "6") (pinfunction "6_6") (pintype "passive"))
      (node (ref "T58") (pin "1") (pinfunction "B_1") (pintype "passive"))
    )
    (net (code "95") (name "/5B9") (class "Default")
      (node (ref "RN70") (pin "7") (pinfunction "7_7") (pintype "passive"))
      (node (ref "T59") (pin "1") (pinfunction "B_1") (pintype "passive"))
    )
    (net (code "96") (name "/5C") (class "Default")
      (node (ref "IC5") (pin "2") (pinfunction "QC_2") (pintype "tri_state"))
      (node (ref "RN50") (pin "2") (pinfunction "2_2") (pintype "passive"))
    )
    (net (code "97") (name "/5C0") (class "Default")
      (node (ref "N5") (pin "K0") (pinfunction "0_K0") (pintype "bidirectional"))
      (node (ref "T50") (pin "3") (pinfunction "C_3") (pintype "passive"))
    )
    (net (code "98") (name "/5C1") (class "Default")
      (node (ref "N5") (pin "K1") (pinfunction "1_K1") (pintype "bidirectional"))
      (node (ref "T51") (pin "3") (pinfunction "C_3") (pintype "passive"))
    )
    (net (code "99") (name "/5C2") (class "Default")
      (node (ref "N5") (pin "K2") (pinfunction "2_K2") (pintype "bidirectional"))
      (node (ref "T52") (pin "3") (pinfunction "C_3") (pintype "passive"))
    )
    (net (code "100") (name "/5C3") (class "Default")
      (node (ref "N5") (pin "K3") (pinfunction "3_K3") (pintype "bidirectional"))
      (node (ref "T53") (pin "3") (pinfunction "C_3") (pintype "passive"))
    )
    (net (code "101") (name "/5C4") (class "Default")
      (node (ref "N5") (pin "K4") (pinfunction "4_K4") (pintype "bidirectional"))
      (node (ref "T54") (pin "3") (pinfunction "C_3") (pintype "passive"))
    )
    (net (code "102") (name "/5C5") (class "Default")
      (node (ref "N5") (pin "K5") (pinfunction "5_K5") (pintype "bidirectional"))
      (node (ref "T55") (pin "3") (pinfunction "C_3") (pintype "passive"))
    )
    (net (code "103") (name "/5C6") (class "Default")
      (node (ref "N5") (pin "K6") (pinfunction "6_K6") (pintype "bidirectional"))
      (node (ref "T56") (pin "3") (pinfunction "C_3") (pintype "passive"))
    )
    (net (code "104") (name "/5C7") (class "Default")
      (node (ref "N5") (pin "K7") (pinfunction "7_K7") (pintype "bidirectional"))
      (node (ref "T57") (pin "3") (pinfunction "C_3") (pintype "passive"))
    )
    (net (code "105") (name "/5C8") (class "Default")
      (node (ref "N5") (pin "K8") (pinfunction "8_K8") (pintype "bidirectional"))
      (node (ref "T58") (pin "3") (pinfunction "C_3") (pintype "passive"))
    )
    (net (code "106") (name "/5C9") (class "Default")
      (node (ref "N5") (pin "K9") (pinfunction "9_K9") (pintype "bidirectional"))
      (node (ref "T59") (pin "3") (pinfunction "C_3") (pintype "passive"))
    )
    (net (code "107") (name "/5D") (class "Default")
      (node (ref "IC5") (pin "3") (pinfunction "QD_3") (pintype "tri_state"))
      (node (ref "RN50") (pin "1") (pinfunction "1_1") (pintype "passive"))
    )
    (net (code "108") (name "/5E") (class "Default")
      (node (ref "IC5") (pin "4") (pinfunction "QE_4") (pintype "tri_state"))
      (node (ref "RN51") (pin "4") (pinfunction "4_4") (pintype "passive"))
    )
    (net (code "109") (name "/5F") (class "Default")
      (node (ref "IC5") (pin "5") (pinfunction "QF_5") (pintype "tri_state"))
      (node (ref "RN51") (pin "3") (pinfunction "3_3") (pintype "passive"))
    )
    (net (code "110") (name "/5G") (class "Default")
      (node (ref "IC5") (pin "6") (pinfunction "QG_6") (pintype "tri_state"))
      (node (ref "RN51") (pin "2") (pinfunction "2_2") (pintype "passive"))
    )
    (net (code "111") (name "/5H") (class "Default")
      (node (ref "IC5") (pin "7") (pinfunction "QH_7") (pintype "tri_state"))
      (node (ref "RN51") (pin "1") (pinfunction "1_1") (pintype "passive"))
    )
    (net (code "112") (name "/6A") (class "Default")
      (node (ref "IC6") (pin "15") (pinfunction "QA_15") (pintype "tri_state"))
      (node (ref "RN60") (pin "4") (pinfunction "4_4") (pintype "passive"))
    )
    (net (code "113") (name "/6B") (class "Default")
      (node (ref "IC6") (pin "1") (pinfunction "QB_1") (pintype "tri_state"))
      (node (ref "RN60") (pin "3") (pinfunction "3_3") (pintype "passive"))
    )
    (net (code "114") (name "/6B0") (class "Default")
      (node (ref "RN81") (pin "6") (pinfunction "6_6") (pintype "passive"))
      (node (ref "T60") (pin "1") (pinfunction "B_1") (pintype "passive"))
    )
    (net (code "115") (name "/6B1") (class "Default")
      (node (ref "RN80") (pin "7") (pinfunction "7_7") (pintype "passive"))
      (node (ref "T61") (pin "1") (pinfunction "B_1") (pintype "passive"))
    )
    (net (code "116") (name "/6B2") (class "Default")
      (node (ref "RN80") (pin "6") (pinfunction "6_6") (pintype "passive"))
      (node (ref "T62") (pin "1") (pinfunction "B_1") (pintype "passive"))
    )
    (net (code "117") (name "/6B3") (class "Default")
      (node (ref "RN80") (pin "5") (pinfunction "5_5") (pintype "passive"))
      (node (ref "T63") (pin "1") (pinfunction "B_1") (pintype "passive"))
    )
    (net (code "118") (name "/6B4") (class "Default")
      (node (ref "RN71") (pin "8") (pinfunction "8_8") (pintype "passive"))
      (node (ref "T64") (pin "1") (pinfunction "B_1") (pintype "passive"))
    )
    (net (code "119") (name "/6B5") (class "Default")
      (node (ref "RN71") (pin "7") (pinfunction "7_7") (pintype "passive"))
      (node (ref "T65") (pin "1") (pinfunction "B_1") (pintype "passive"))
    )
    (net (code "120") (name "/6B6") (class "Default")
      (node (ref "RN81") (pin "8") (pinfunction "8_8") (pintype "passive"))
      (node (ref "T66") (pin "1") (pinfunction "B_1") (pintype "passive"))
    )
    (net (code "121") (name "/6B7") (class "Default")
      (node (ref "RN81") (pin "7") (pinfunction "7_7") (pintype "passive"))
      (node (ref "T67") (pin "1") (pinfunction "B_1") (pintype "passive"))
    )
    (net (code "122") (name "/6B8") (class "Default")
      (node (ref "RN80") (pin "8") (pinfunction "8_8") (pintype "passive"))
      (node (ref "T68") (pin "1") (pinfunction "B_1") (pintype "passive"))
    )
    (net (code "123") (name "/6B9") (class "Default")
      (node (ref "RN81") (pin "5") (pinfunction "5_5") (pintype "passive"))
      (node (ref "T69") (pin "1") (pinfunction "B_1") (pintype "passive"))
    )
    (net (code "124") (name "/6C") (class "Default")
      (node (ref "IC6") (pin "2") (pinfunction "QC_2") (pintype "tri_state"))
      (node (ref "RN60") (pin "2") (pinfunction "2_2") (pintype "passive"))
    )
    (net (code "125") (name "/6C0") (class "Default")
      (node (ref "N6") (pin "K0") (pinfunction "0_K0") (pintype "bidirectional"))
      (node (ref "T60") (pin "3") (pinfunction "C_3") (pintype "passive"))
    )
    (net (code "126") (name "/6C1") (class "Default")
      (node (ref "N6") (pin "K1") (pinfunction "1_K1") (pintype "bidirectional"))
      (node (ref "T61") (pin "3") (pinfunction "C_3") (pintype "passive"))
    )
    (net (code "127") (name "/6C2") (class "Default")
      (node (ref "N6") (pin "K2") (pinfunction "2_K2") (pintype "bidirectional"))
      (node (ref "T62") (pin "3") (pinfunction "C_3") (pintype "passive"))
    )
    (net (code "128") (name "/6C3") (class "Default")
      (node (ref "N6") (pin "K3") (pinfunction "3_K3") (pintype "bidirectional"))
      (node (ref "T63") (pin "3") (pinfunction "C_3") (pintype "passive"))
    )
    (net (code "129") (name "/6C4") (class "Default")
      (node (ref "N6") (pin "K4") (pinfunction "4_K4") (pintype "bidirectional"))
      (node (ref "T64") (pin "3") (pinfunction "C_3") (pintype "passive"))
    )
    (net (code "130") (name "/6C5") (class "Default")
      (node (ref "N6") (pin "K5") (pinfunction "5_K5") (pintype "bidirectional"))
      (node (ref "T65") (pin "3") (pinfunction "C_3") (pintype "passive"))
    )
    (net (code "131") (name "/6C6") (class "Default")
      (node (ref "N6") (pin "K6") (pinfunction "6_K6") (pintype "bidirectional"))
      (node (ref "T66") (pin "3") (pinfunction "C_3") (pintype "passive"))
    )
    (net (code "132") (name "/6C7") (class "Default")
      (node (ref "N6") (pin "K7") (pinfunction "7_K7") (pintype "bidirectional"))
      (node (ref "T67") (pin "3") (pinfunction "C_3") (pintype "passive"))
    )
    (net (code "133") (name "/6C8") (class "Default")
      (node (ref "N6") (pin "K8") (pinfunction "8_K8") (pintype "bidirectional"))
      (node (ref "T68") (pin "3") (pinfunction "C_3") (pintype "passive"))
    )
    (net (code "134") (name "/6C9") (class "Default")
      (node (ref "N6") (pin "K9") (pinfunction "9_K9") (pintype "bidirectional"))
      (node (ref "T69") (pin "3") (pinfunction "C_3") (pintype "passive"))
    )
    (net (code "135") (name "/6D") (class "Default")
      (node (ref "IC6") (pin "3") (pinfunction "QD_3") (pintype "tri_state"))
      (node (ref "RN60") (pin "1") (pinfunction "1_1") (pintype "passive"))
    )
    (net (code "136") (name "/6E") (class "Default")
      (node (ref "IC6") (pin "4") (pinfunction "QE_4") (pintype "tri_state"))
      (node (ref "RN61") (pin "4") (pinfunction "4_4") (pintype "passive"))
    )
    (net (code "137") (name "/6F") (class "Default")
      (node (ref "IC6") (pin "5") (pinfunction "QF_5") (pintype "tri_state"))
      (node (ref "RN61") (pin "3") (pinfunction "3_3") (pintype "passive"))
    )
    (net (code "138") (name "/6G") (class "Default")
      (node (ref "IC6") (pin "6") (pinfunction "QG_6") (pintype "tri_state"))
      (node (ref "RN61") (pin "2") (pinfunction "2_2") (pintype "passive"))
    )
    (net (code "139") (name "/6H") (class "Default")
      (node (ref "IC6") (pin "7") (pinfunction "QH_7") (pintype "tri_state"))
      (node (ref "RN61") (pin "1") (pinfunction "1_1") (pintype "passive"))
    )
    (net (code "140") (name "/7A") (class "Default")
      (node (ref "IC7") (pin "15") (pinfunction "QA_15") (pintype "tri_state"))
      (node (ref "RN70") (pin "4") (pinfunction "4_4") (pintype "passive"))
    )
    (net (code "141") (name "/7B") (class "Default")
      (node (ref "IC7") (pin "1") (pinfunction "QB_1") (pintype "tri_state"))
      (node (ref "RN70") (pin "3") (pinfunction "3_3") (pintype "passive"))
    )
    (net (code "142") (name "/7C") (class "Default")
      (node (ref "IC7") (pin "2") (pinfunction "QC_2") (pintype "tri_state"))
      (node (ref "RN70") (pin "2") (pinfunction "2_2") (pintype "passive"))
    )
    (net (code "143") (name "/7D") (class "Default")
      (node (ref "IC7") (pin "3") (pinfunction "QD_3") (pintype "tri_state"))
      (node (ref "RN70") (pin "1") (pinfunction "1_1") (pintype "passive"))
    )
    (net (code "144") (name "/7E") (class "Default")
      (node (ref "IC7") (pin "4") (pinfunction "QE_4") (pintype "tri_state"))
      (node (ref "RN71") (pin "4") (pinfunction "4_4") (pintype "passive"))
    )
    (net (code "145") (name "/7F") (class "Default")
      (node (ref "IC7") (pin "5") (pinfunction "QF_5") (pintype "tri_state"))
      (node (ref "RN71") (pin "3") (pinfunction "3_3") (pintype "passive"))
    )
    (net (code "146") (name "/7G") (class "Default")
      (node (ref "IC7") (pin "6") (pinfunction "QG_6") (pintype "tri_state"))
      (node (ref "RN71") (pin "2") (pinfunction "2_2") (pintype "passive"))
    )
    (net (code "147") (name "/7H") (class "Default")
      (node (ref "IC7") (pin "7") (pinfunction "QH_7") (pintype "tri_state"))
      (node (ref "RN71") (pin "1") (pinfunction "1_1") (pintype "passive"))
    )
    (net (code "148") (name "/8A") (class "Default")
      (node (ref "IC8") (pin "15") (pinfunction "QA_15") (pintype "tri_state"))
      (node (ref "RN80") (pin "4") (pinfunction "4_4") (pintype "passive"))
    )
    (net (code "149") (name "/8B") (class "Default")
      (node (ref "IC8") (pin "1") (pinfunction "QB_1") (pintype "tri_state"))
      (node (ref "RN80") (pin "3") (pinfunction "3_3") (pintype "passive"))
    )
    (net (code "150") (name "/8C") (class "Default")
      (node (ref "IC8") (pin "2") (pinfunction "QC_2") (pintype "tri_state"))
      (node (ref "RN80") (pin "2") (pinfunction "2_2") (pintype "passive"))
    )
    (net (code "151") (name "/8D") (class "Default")
      (node (ref "IC8") (pin "3") (pinfunction "QD_3") (pintype "tri_state"))
      (node (ref "RN80") (pin "1") (pinfunction "1_1") (pintype "passive"))
    )
    (net (code "152") (name "/8E") (class "Default")
      (node (ref "IC8") (pin "4") (pinfunction "QE_4") (pintype "tri_state"))
      (node (ref "RN81") (pin "4") (pinfunction "4_4") (pintype "passive"))
    )
    (net (code "153") (name "/8F") (class "Default")
      (node (ref "IC8") (pin "5") (pinfunction "QF_5") (pintype "tri_state"))
      (node (ref "RN81") (pin "3") (pinfunction "3_3") (pintype "passive"))
    )
    (net (code "154") (name "/8G") (class "Default")
      (node (ref "IC8") (pin "6") (pinfunction "QG_6") (pintype "tri_state"))
      (node (ref "RN81") (pin "2") (pinfunction "2_2") (pintype "passive"))
    )
    (net (code "155") (name "/8H") (class "Default")
      (node (ref "IC8") (pin "7") (pinfunction "QH_7") (pintype "tri_state"))
      (node (ref "RN81") (pin "1") (pinfunction "1_1") (pintype "passive"))
    )
    (net (code "156") (name "/EN") (class "Default")
      (node (ref "IC1") (pin "13") (pinfunction "G_13") (pintype "input"))
      (node (ref "IC2") (pin "13") (pinfunction "G_13") (pintype "input"))
      (node (ref "IC3") (pin "13") (pinfunction "G_13") (pintype "input"))
      (node (ref "IC4") (pin "13") (pinfunction "G_13") (pintype "input"))
      (node (ref "IC5") (pin "13") (pinfunction "G_13") (pintype "input"))
      (node (ref "IC6") (pin "13") (pinfunction "G_13") (pintype "input"))
      (node (ref "IC7") (pin "13") (pinfunction "G_13") (pintype "input"))
      (node (ref "IC8") (pin "13") (pinfunction "G_13") (pintype "input"))
      (node (ref "JP1") (pin "1") (pinfunction "1_1") (pintype "passive"))
    )
    (net (code "157") (name "/GL1") (class "Default")
      (node (ref "RN31") (pin "5") (pinfunction "5_5") (pintype "passive"))
      (node (ref "T1") (pin "1") (pinfunction "B_1") (pintype "passive"))
    )
    (net (code "158") (name "/GL2") (class "Default")
      (node (ref "RN31") (pin "6") (pinfunction "6_6") (pintype "passive"))
      (node (ref "T2") (pin "1") (pinfunction "B_1") (pintype "passive"))
    )
    (net (code "159") (name "/GL3") (class "Default")
      (node (ref "RN60") (pin "7") (pinfunction "7_7") (pintype "passive"))
      (node (ref "T3") (pin "1") (pinfunction "B_1") (pintype "passive"))
    )
    (net (code "160") (name "/GL4") (class "Default")
      (node (ref "RN60") (pin "8") (pinfunction "8_8") (pintype "passive"))
      (node (ref "T4") (pin "1") (pinfunction "B_1") (pintype "passive"))
    )
    (net (code "161") (name "/MOSI") (class "Default")
      (node (ref "IC1") (pin "14") (pinfunction "SER_14") (pintype "input"))
      (node (ref "JP1") (pin "4") (pinfunction "4_4") (pintype "passive"))
    )
    (net (code "162") (name "/N1_0") (class "Default")
      (node (ref "N1") (pin "K0") (pinfunction "0_K0") (pintype "bidirectional"))
      (node (ref "T10") (pin "3") (pinfunction "C_3") (pintype "passive"))
    )
    (net (code "163") (name "/N1_1") (class "Default")
      (node (ref "N1") (pin "K1") (pinfunction "1_K1") (pintype "bidirectional"))
      (node (ref "T11") (pin "3") (pinfunction "C_3") (pintype "passive"))
    )
    (net (code "164") (name "/N1_2") (class "Default")
      (node (ref "N1") (pin "K2") (pinfunction "2_K2") (pintype "bidirectional"))
      (node (ref "T12") (pin "3") (pinfunction "C_3") (pintype "passive"))
    )
    (net (code "165") (name "/N1_3") (class "Default")
      (node (ref "N1") (pin "K3") (pinfunction "3_K3") (pintype "bidirectional"))
      (node (ref "T13") (pin "3") (pinfunction "C_3") (pintype "passive"))
    )
    (net (code "166") (name "/N1_4") (class "Default")
      (node (ref "N1") (pin "K4") (pinfunction "4_K4") (pintype "bidirectional"))
      (node (ref "T14") (pin "3") (pinfunction "C_3") (pintype "passive"))
    )
    (net (code "167") (name "/N1_5") (class "Default")
      (node (ref "N1") (pin "K5") (pinfunction "5_K5") (pintype "bidirectional"))
      (node (ref "T15") (pin "3") (pinfunction "C_3") (pintype "passive"))
    )
    (net (code "168") (name "/N1_6") (class "Default")
      (node (ref "N1") (pin "K6") (pinfunction "6_K6") (pintype "bidirectional"))
      (node (ref "T16") (pin "3") (pinfunction "C_3") (pintype "passive"))
    )
    (net (code "169") (name "/N1_7") (class "Default")
      (node (ref "N1") (pin "K7") (pinfunction "7_K7") (pintype "bidirectional"))
      (node (ref "T17") (pin "3") (pinfunction "C_3") (pintype "passive"))
    )
    (net (code "170") (name "/N1_8") (class "Default")
      (node (ref "N1") (pin "K8") (pinfunction "8_K8") (pintype "bidirectional"))
      (node (ref "T18") (pin "3") (pinfunction "C_3") (pintype "passive"))
    )
    (net (code "171") (name "/N1_9") (class "Default")
      (node (ref "N1") (pin "K9") (pinfunction "9_K9") (pintype "bidirectional"))
      (node (ref "T19") (pin "3") (pinfunction "C_3") (pintype "passive"))
    )
    (net (code "172") (name "/N1_DP") (class "Default")
      (node (ref "N1") (pin "KDP") (pinfunction "DP_KDP") (pintype "bidirectional"))
    )
    (net (code "173") (name "/N2_0") (class "Default")
      (node (ref "N2") (pin "K0") (pinfunction "0_K0") (pintype "bidirectional"))
      (node (ref "T20") (pin "3") (pinfunction "C_3") (pintype "passive"))
    )
    (net (code "174") (name "/N2_1") (class "Default")
      (node (ref "N2") (pin "K1") (pinfunction "1_K1") (pintype "bidirectional"))
      (node (ref "T21") (pin "3") (pinfunction "C_3") (pintype "passive"))
    )
    (net (code "175") (name "/N2_2") (class "Default")
      (node (ref "N2") (pin "K2") (pinfunction "2_K2") (pintype "bidirectional"))
      (node (ref "T22") (pin "3") (pinfunction "C_3") (pintype "passive"))
    )
    (net (code "176") (name "/N2_3") (class "Default")
      (node (ref "N2") (pin "K3") (pinfunction "3_K3") (pintype "bidirectional"))
      (node (ref "T23") (pin "3") (pinfunction "C_3") (pintype "passive"))
    )
    (net (code "177") (name "/N2_4") (class "Default")
      (node (ref "N2") (pin "K4") (pinfunction "4_K4") (pintype "bidirectional"))
      (node (ref "T24") (pin "3") (pinfunction "C_3") (pintype "passive"))
    )
    (net (code "178") (name "/N2_5") (class "Default")
      (node (ref "N2") (pin "K5") (pinfunction "5_K5") (pintype "bidirectional"))
      (node (ref "T25") (pin "3") (pinfunction "C_3") (pintype "passive"))
    )
    (net (code "179") (name "/N2_6") (class "Default")
      (node (ref "N2") (pin "K6") (pinfunction "6_K6") (pintype "bidirectional"))
      (node (ref "T26") (pin "3") (pinfunction "C_3") (pintype "passive"))
    )
    (net (code "180") (name "/N2_7") (class "Default")
      (node (ref "N2") (pin "K7") (pinfunction "7_K7") (pintype "bidirectional"))
      (node (ref "T27") (pin "3") (pinfunction "C_3") (pintype "passive"))
    )
    (net (code "181") (name "/N2_8") (class "Default")
      (node (ref "N2") (pin "K8") (pinfunction "8_K8") (pintype "bidirectional"))
      (node (ref "T28") (pin "3") (pinfunction "C_3") (pintype "passive"))
    )
    (net (code "182") (name "/N2_9") (class "Default")
      (node (ref "N2") (pin "K9") (pinfunction "9_K9") (pintype "bidirectional"))
      (node (ref "T29") (pin "3") (pinfunction "C_3") (pintype "passive"))
    )
    (net (code "183") (name "/N3_0") (class "Default")
      (node (ref "N3") (pin "K0") (pinfunction "0_K0") (pintype "bidirectional"))
      (node (ref "T30") (pin "3") (pinfunction "C_3") (pintype "passive"))
    )
    (net (code "184") (name "/N3_1") (class "Default")
      (node (ref "N3") (pin "K1") (pinfunction "1_K1") (pintype "bidirectional"))
      (node (ref "T31") (pin "3") (pinfunction "C_3") (pintype "passive"))
    )
    (net (code "185") (name "/N3_2") (class "Default")
      (node (ref "N3") (pin "K2") (pinfunction "2_K2") (pintype "bidirectional"))
      (node (ref "T32") (pin "3") (pinfunction "C_3") (pintype "passive"))
    )
    (net (code "186") (name "/N3_3") (class "Default")
      (node (ref "N3") (pin "K3") (pinfunction "3_K3") (pintype "bidirectional"))
      (node (ref "T33") (pin "3") (pinfunction "C_3") (pintype "passive"))
    )
    (net (code "187") (name "/N3_4") (class "Default")
      (node (ref "N3") (pin "K4") (pinfunction "4_K4") (pintype "bidirectional"))
      (node (ref "T34") (pin "3") (pinfunction "C_3") (pintype "passive"))
    )
    (net (code "188") (name "/N3_5") (class "Default")
      (node (ref "N3") (pin "K5") (pinfunction "5_K5") (pintype "bidirectional"))
      (node (ref "T35") (pin "3") (pinfunction "C_3") (pintype "passive"))
    )
    (net (code "189") (name "/N3_6") (class "Default")
      (node (ref "N3") (pin "K6") (pinfunction "6_K6") (pintype "bidirectional"))
      (node (ref "T36") (pin "3") (pinfunction "C_3") (pintype "passive"))
    )
    (net (code "190") (name "/N3_7") (class "Default")
      (node (ref "N3") (pin "K7") (pinfunction "7_K7") (pintype "bidirectional"))
      (node (ref "T37") (pin "3") (pinfunction "C_3") (pintype "passive"))
    )
    (net (code "191") (name "/N3_8") (class "Default")
      (node (ref "N3") (pin "K8") (pinfunction "8_K8") (pintype "bidirectional"))
      (node (ref "T38") (pin "3") (pinfunction "C_3") (pintype "passive"))
    )
    (net (code "192") (name "/N3_9") (class "Default")
      (node (ref "N3") (pin "K9") (pinfunction "9_K9") (pintype "bidirectional"))
      (node (ref "T39") (pin "3") (pinfunction "C_3") (pintype "passive"))
    )
    (net (code "193") (name "/RCK") (class "Default")
      (node (ref "IC1") (pin "12") (pinfunction "RCK_12") (pintype "input"))
      (node (ref "IC2") (pin "12") (pinfunction "RCK_12") (pintype "input"))
      (node (ref "IC3") (pin "12") (pinfunction "RCK_12") (pintype "input"))
      (node (ref "IC4") (pin "12") (pinfunction "RCK_12") (pintype "input"))
      (node (ref "IC5") (pin "12") (pinfunction "RCK_12") (pintype "input"))
      (node (ref "IC6") (pin "12") (pinfunction "RCK_12") (pintype "input"))
      (node (ref "IC7") (pin "12") (pinfunction "RCK_12") (pintype "input"))
      (node (ref "IC8") (pin "12") (pinfunction "RCK_12") (pintype "input"))
      (node (ref "JP1") (pin "5") (pinfunction "5_5") (pintype "passive"))
    )
    (net (code "194") (name "/SCK") (class "Default")
      (node (ref "IC1") (pin "11") (pinfunction "SCK_11") (pintype "input"))
      (node (ref "IC2") (pin "11") (pinfunction "SCK_11") (pintype "input"))
      (node (ref "IC3") (pin "11") (pinfunction "SCK_11") (pintype "input"))
      (node (ref "IC4") (pin "11") (pinfunction "SCK_11") (pintype "input"))
      (node (ref "IC5") (pin "11") (pinfunction "SCK_11") (pintype "input"))
      (node (ref "IC6") (pin "11") (pinfunction "SCK_11") (pintype "input"))
      (node (ref "IC7") (pin "11") (pinfunction "SCK_11") (pintype "input"))
      (node (ref "IC8") (pin "11") (pinfunction "SCK_11") (pintype "input"))
      (node (ref "JP1") (pin "3") (pinfunction "3_3") (pintype "passive"))
    )
    (net (code "195") (name "/SCL") (class "Default")
      (node (ref "IC1") (pin "10") (pinfunction "SCL_10") (pintype "input"))
      (node (ref "IC2") (pin "10") (pinfunction "SCL_10") (pintype "input"))
      (node (ref "IC3") (pin "10") (pinfunction "SCL_10") (pintype "input"))
      (node (ref "IC4") (pin "10") (pinfunction "SCL_10") (pintype "input"))
      (node (ref "IC5") (pin "10") (pinfunction "SCL_10") (pintype "input"))
      (node (ref "IC6") (pin "10") (pinfunction "SCL_10") (pintype "input"))
      (node (ref "IC7") (pin "10") (pinfunction "SCL_10") (pintype "input"))
      (node (ref "IC8") (pin "10") (pinfunction "SCL_10") (pintype "input"))
      (node (ref "JP1") (pin "2") (pinfunction "2_2") (pintype "passive"))
    )
    (net (code "196") (name "GND") (class "Default")
      (node (ref "C1") (pin "2") (pinfunction "2_2") (pintype "passive"))
      (node (ref "C2") (pin "2") (pinfunction "2_2") (pintype "passive"))
      (node (ref "C3") (pin "2") (pinfunction "2_2") (pintype "passive"))
      (node (ref "C4") (pin "2") (pinfunction "2_2") (pintype "passive"))
      (node (ref "C5") (pin "2") (pinfunction "2_2") (pintype "passive"))
      (node (ref "C6") (pin "2") (pinfunction "2_2") (pintype "passive"))
      (node (ref "C7") (pin "2") (pinfunction "2_2") (pintype "passive"))
      (node (ref "C8") (pin "2") (pinfunction "2_2") (pintype "passive"))
      (node (ref "IC1") (pin "8") (pinfunction "GND_8") (pintype "power_in"))
      (node (ref "IC2") (pin "8") (pinfunction "GND_8") (pintype "power_in"))
      (node (ref "IC3") (pin "8") (pinfunction "GND_8") (pintype "power_in"))
      (node (ref "IC4") (pin "8") (pinfunction "GND_8") (pintype "power_in"))
      (node (ref "IC5") (pin "8") (pinfunction "GND_8") (pintype "power_in"))
      (node (ref "IC6") (pin "8") (pinfunction "GND_8") (pintype "power_in"))
      (node (ref "IC7") (pin "8") (pinfunction "GND_8") (pintype "power_in"))
      (node (ref "IC8") (pin "8") (pinfunction "GND_8") (pintype "power_in"))
      (node (ref "JP1") (pin "6") (pinfunction "6_6") (pintype "passive"))
      (node (ref "JP2") (pin "2") (pinfunction "2_2") (pintype "passive"))
      (node (ref "JP2") (pin "3") (pinfunction "3_3") (pintype "passive"))
      (node (ref "JP2") (pin "4") (pinfunction "4_4") (pintype "passive"))
      (node (ref "JP2") (pin "5") (pinfunction "5_5") (pintype "passive"))
      (node (ref "R11") (pin "1") (pinfunction "1_1") (pintype "passive"))
      (node (ref "R21") (pin "1") (pinfunction "1_1") (pintype "passive"))
      (node (ref "R31") (pin "1") (pinfunction "1_1") (pintype "passive"))
      (node (ref "R41") (pin "1") (pinfunction "1_1") (pintype "passive"))
      (node (ref "R51") (pin "1") (pinfunction "1_1") (pintype "passive"))
      (node (ref "R61") (pin "1") (pinfunction "1_1") (pintype "passive"))
      (node (ref "T1") (pin "2") (pinfunction "E_2") (pintype "passive"))
      (node (ref "T10") (pin "2") (pinfunction "E_2") (pintype "passive"))
      (node (ref "T11") (pin "2") (pinfunction "E_2") (pintype "passive"))
      (node (ref "T12") (pin "2") (pinfunction "E_2") (pintype "passive"))
      (node (ref "T13") (pin "2") (pinfunction "E_2") (pintype "passive"))
      (node (ref "T14") (pin "2") (pinfunction "E_2") (pintype "passive"))
      (node (ref "T15") (pin "2") (pinfunction "E_2") (pintype "passive"))
      (node (ref "T16") (pin "2") (pinfunction "E_2") (pintype "passive"))
      (node (ref "T17") (pin "2") (pinfunction "E_2") (pintype "passive"))
      (node (ref "T18") (pin "2") (pinfunction "E_2") (pintype "passive"))
      (node (ref "T19") (pin "2") (pinfunction "E_2") (pintype "passive"))
      (node (ref "T2") (pin "2") (pinfunction "E_2") (pintype "passive"))
      (node (ref "T20") (pin "2") (pinfunction "E_2") (pintype "passive"))
      (node (ref "T21") (pin "2") (pinfunction "E_2") (pintype "passive"))
      (node (ref "T22") (pin "2") (pinfunction "E_2") (pintype "passive"))
      (node (ref "T23") (pin "2") (pinfunction "E_2") (pintype "passive"))
      (node (ref "T24") (pin "2") (pinfunction "E_2") (pintype "passive"))
      (node (ref "T25") (pin "2") (pinfunction "E_2") (pintype "passive"))
      (node (ref "T26") (pin "2") (pinfunction "E_2") (pintype "passive"))
      (node (ref "T27") (pin "2") (pinfunction "E_2") (pintype "passive"))
      (node (ref "T28") (pin "2") (pinfunction "E_2") (pintype "passive"))
      (node (ref "T29") (pin "2") (pinfunction "E_2") (pintype "passive"))
      (node (ref "T3") (pin "2") (pinfunction "E_2") (pintype "passive"))
      (node (ref "T30") (pin "2") (pinfunction "E_2") (pintype "passive"))
      (node (ref "T31") (pin "2") (pinfunction "E_2") (pintype "passive"))
      (node (ref "T32") (pin "2") (pinfunction "E_2") (pintype "passive"))
      (node (ref "T33") (pin "2") (pinfunction "E_2") (pintype "passive"))
      (node (ref "T34") (pin "2") (pinfunction "E_2") (pintype "passive"))
      (node (ref "T35") (pin "2") (pinfunction "E_2") (pintype "passive"))
      (node (ref "T36") (pin "2") (pinfunction "E_2") (pintype "passive"))
      (node (ref "T37") (pin "2") (pinfunction "E_2") (pintype "passive"))
      (node (ref "T38") (pin "2") (pinfunction "E_2") (pintype "passive"))
      (node (ref "T39") (pin "2") (pinfunction "E_2") (pintype "passive"))
      (node (ref "T4") (pin "2") (pinfunction "E_2") (pintype "passive"))
      (node (ref "T40") (pin "2") (pinfunction "E_2") (pintype "passive"))
      (node (ref "T41") (pin "2") (pinfunction "E_2") (pintype "passive"))
      (node (ref "T42") (pin "2") (pinfunction "E_2") (pintype "passive"))
      (node (ref "T43") (pin "2") (pinfunction "E_2") (pintype "passive"))
      (node (ref "T44") (pin "2") (pinfunction "E_2") (pintype "passive"))
      (node (ref "T45") (pin "2") (pinfunction "E_2") (pintype "passive"))
      (node (ref "T46") (pin "2") (pinfunction "E_2") (pintype "passive"))
      (node (ref "T47") (pin "2") (pinfunction "E_2") (pintype "passive"))
      (node (ref "T48") (pin "2") (pinfunction "E_2") (pintype "passive"))
      (node (ref "T49") (pin "2") (pinfunction "E_2") (pintype "passive"))
      (node (ref "T50") (pin "2") (pinfunction "E_2") (pintype "passive"))
      (node (ref "T51") (pin "2") (pinfunction "E_2") (pintype "passive"))
      (node (ref "T52") (pin "2") (pinfunction "E_2") (pintype "passive"))
      (node (ref "T53") (pin "2") (pinfunction "E_2") (pintype "passive"))
      (node (ref "T54") (pin "2") (pinfunction "E_2") (pintype "passive"))
      (node (ref "T55") (pin "2") (pinfunction "E_2") (pintype "passive"))
      (node (ref "T56") (pin "2") (pinfunction "E_2") (pintype "passive"))
      (node (ref "T57") (pin "2") (pinfunction "E_2") (pintype "passive"))
      (node (ref "T58") (pin "2") (pinfunction "E_2") (pintype "passive"))
      (node (ref "T59") (pin "2") (pinfunction "E_2") (pintype "passive"))
      (node (ref "T60") (pin "2") (pinfunction "E_2") (pintype "passive"))
      (node (ref "T61") (pin "2") (pinfunction "E_2") (pintype "passive"))
      (node (ref "T62") (pin "2") (pinfunction "E_2") (pintype "passive"))
      (node (ref "T63") (pin "2") (pinfunction "E_2") (pintype "passive"))
      (node (ref "T64") (pin "2") (pinfunction "E_2") (pintype "passive"))
      (node (ref "T65") (pin "2") (pinfunction "E_2") (pintype "passive"))
      (node (ref "T66") (pin "2") (pinfunction "E_2") (pintype "passive"))
      (node (ref "T67") (pin "2") (pinfunction "E_2") (pintype "passive"))
      (node (ref "T68") (pin "2") (pinfunction "E_2") (pintype "passive"))
      (node (ref "T69") (pin "2") (pinfunction "E_2") (pintype "passive"))
    )
    (net (code "197") (name "Net-(GL1-A)") (class "Default")
      (node (ref "GL1") (pin "1") (pinfunction "A_1") (pintype "passive"))
      (node (ref "R1") (pin "1") (pinfunction "1_1") (pintype "passive"))
    )
    (net (code "198") (name "Net-(GL1-A1)") (class "Default")
      (node (ref "GL1") (pin "2") (pinfunction "A1_2") (pintype "passive"))
      (node (ref "T1") (pin "3") (pinfunction "C_3") (pintype "passive"))
    )
    (net (code "199") (name "Net-(GL2-A)") (class "Default")
      (node (ref "GL2") (pin "1") (pinfunction "A_1") (pintype "passive"))
      (node (ref "R2") (pin "1") (pinfunction "1_1") (pintype "passive"))
    )
    (net (code "200") (name "Net-(GL2-A1)") (class "Default")
      (node (ref "GL2") (pin "2") (pinfunction "A1_2") (pintype "passive"))
      (node (ref "T2") (pin "3") (pinfunction "C_3") (pintype "passive"))
    )
    (net (code "201") (name "Net-(GL3-A)") (class "Default")
      (node (ref "GL3") (pin "1") (pinfunction "A_1") (pintype "passive"))
      (node (ref "R3") (pin "1") (pinfunction "1_1") (pintype "passive"))
    )
    (net (code "202") (name "Net-(GL3-A1)") (class "Default")
      (node (ref "GL3") (pin "2") (pinfunction "A1_2") (pintype "passive"))
      (node (ref "T3") (pin "3") (pinfunction "C_3") (pintype "passive"))
    )
    (net (code "203") (name "Net-(GL4-A)") (class "Default")
      (node (ref "GL4") (pin "1") (pinfunction "A_1") (pintype "passive"))
      (node (ref "R4") (pin "1") (pinfunction "1_1") (pintype "passive"))
    )
    (net (code "204") (name "Net-(GL4-A1)") (class "Default")
      (node (ref "GL4") (pin "2") (pinfunction "A1_2") (pintype "passive"))
      (node (ref "T4") (pin "3") (pinfunction "C_3") (pintype "passive"))
    )
    (net (code "205") (name "Net-(IC1A-QH*)") (class "Default")
      (node (ref "IC1") (pin "9") (pinfunction "QH*_9") (pintype "tri_state"))
      (node (ref "IC2") (pin "14") (pinfunction "SER_14") (pintype "input"))
    )
    (net (code "206") (name "Net-(IC2A-QH*)") (class "Default")
      (node (ref "IC2") (pin "9") (pinfunction "QH*_9") (pintype "tri_state"))
      (node (ref "IC3") (pin "14") (pinfunction "SER_14") (pintype "input"))
    )
    (net (code "207") (name "Net-(IC3A-QH*)") (class "Default")
      (node (ref "IC3") (pin "9") (pinfunction "QH*_9") (pintype "tri_state"))
      (node (ref "IC4") (pin "14") (pinfunction "SER_14") (pintype "input"))
    )
    (net (code "208") (name "Net-(IC4A-QH*)") (class "Default")
      (node (ref "IC4") (pin "9") (pinfunction "QH*_9") (pintype "tri_state"))
      (node (ref "IC5") (pin "14") (pinfunction "SER_14") (pintype "input"))
    )
    (net (code "209") (name "Net-(IC5A-QH*)") (class "Default")
      (node (ref "IC5") (pin "9") (pinfunction "QH*_9") (pintype "tri_state"))
      (node (ref "IC6") (pin "14") (pinfunction "SER_14") (pintype "input"))
    )
    (net (code "210") (name "Net-(IC6A-QH*)") (class "Default")
      (node (ref "IC6") (pin "9") (pinfunction "QH*_9") (pintype "tri_state"))
      (node (ref "IC7") (pin "14") (pinfunction "SER_14") (pintype "input"))
    )
    (net (code "211") (name "Net-(IC7A-QH*)") (class "Default")
      (node (ref "IC7") (pin "9") (pinfunction "QH*_9") (pintype "tri_state"))
      (node (ref "IC8") (pin "14") (pinfunction "SER_14") (pintype "input"))
    )
    (net (code "212") (name "Net-(N1-A-PadA1)") (class "Default")
      (node (ref "N1") (pin "A1") (pinfunction "A_A1") (pintype "bidirectional"))
      (node (ref "N1") (pin "A2") (pinfunction "A_A2") (pintype "bidirectional"))
      (node (ref "R10") (pin "1") (pinfunction "1_1") (pintype "passive"))
    )
    (net (code "213") (name "Net-(N1-PadPR)") (class "Default")
      (node (ref "N1") (pin "PR") (pinfunction "PR_PR") (pintype "bidirectional"))
      (node (ref "R11") (pin "2") (pinfunction "2_2") (pintype "passive"))
    )
    (net (code "214") (name "Net-(N2-A-PadA1)") (class "Default")
      (node (ref "N2") (pin "A1") (pinfunction "A_A1") (pintype "bidirectional"))
      (node (ref "N2") (pin "A2") (pinfunction "A_A2") (pintype "bidirectional"))
      (node (ref "R20") (pin "1") (pinfunction "1_1") (pintype "passive"))
    )
    (net (code "215") (name "Net-(N2-PadPR)") (class "Default")
      (node (ref "N2") (pin "PR") (pinfunction "PR_PR") (pintype "bidirectional"))
      (node (ref "R21") (pin "2") (pinfunction "2_2") (pintype "passive"))
    )
    (net (code "216") (name "Net-(N3-A-PadA1)") (class "Default")
      (node (ref "N3") (pin "A1") (pinfunction "A_A1") (pintype "bidirectional"))
      (node (ref "N3") (pin "A2") (pinfunction "A_A2") (pintype "bidirectional"))
      (node (ref "R30") (pin "1") (pinfunction "1_1") (pintype "passive"))
    )
    (net (code "217") (name "Net-(N3-PadPR)") (class "Default")
      (node (ref "N3") (pin "PR") (pinfunction "PR_PR") (pintype "bidirectional"))
      (node (ref "R31") (pin "2") (pinfunction "2_2") (pintype "passive"))
    )
    (net (code "218") (name "Net-(N4-A-PadA1)") (class "Default")
      (node (ref "N4") (pin "A1") (pinfunction "A_A1") (pintype "bidirectional"))
      (node (ref "N4") (pin "A2") (pinfunction "A_A2") (pintype "bidirectional"))
      (node (ref "R40") (pin "1") (pinfunction "1_1") (pintype "passive"))
    )
    (net (code "219") (name "Net-(N4-PadPR)") (class "Default")
      (node (ref "N4") (pin "PR") (pinfunction "PR_PR") (pintype "bidirectional"))
      (node (ref "R41") (pin "2") (pinfunction "2_2") (pintype "passive"))
    )
    (net (code "220") (name "Net-(N5-A-PadA1)") (class "Default")
      (node (ref "N5") (pin "A1") (pinfunction "A_A1") (pintype "bidirectional"))
      (node (ref "N5") (pin "A2") (pinfunction "A_A2") (pintype "bidirectional"))
      (node (ref "R50") (pin "1") (pinfunction "1_1") (pintype "passive"))
    )
    (net (code "221") (name "Net-(N5-PadPR)") (class "Default")
      (node (ref "N5") (pin "PR") (pinfunction "PR_PR") (pintype "bidirectional"))
      (node (ref "R51") (pin "2") (pinfunction "2_2") (pintype "passive"))
    )
    (net (code "222") (name "Net-(N6-A-PadA1)") (class "Default")
      (node (ref "N6") (pin "A1") (pinfunction "A_A1") (pintype "bidirectional"))
      (node (ref "N6") (pin "A2") (pinfunction "A_A2") (pintype "bidirectional"))
      (node (ref "R60") (pin "1") (pinfunction "1_1") (pintype "passive"))
    )
    (net (code "223") (name "Net-(N6-PadPR)") (class "Default")
      (node (ref "N6") (pin "PR") (pinfunction "PR_PR") (pintype "bidirectional"))
      (node (ref "R61") (pin "2") (pinfunction "2_2") (pintype "passive"))
    )
    (net (code "224") (name "VDD") (class "Default")
      (node (ref "JP2") (pin "1") (pinfunction "1_1") (pintype "passive"))
      (node (ref "R1") (pin "2") (pinfunction "2_2") (pintype "passive"))
      (node (ref "R10") (pin "2") (pinfunction "2_2") (pintype "passive"))
      (node (ref "R2") (pin "2") (pinfunction "2_2") (pintype "passive"))
      (node (ref "R20") (pin "2") (pinfunction "2_2") (pintype "passive"))
      (node (ref "R3") (pin "2") (pinfunction "2_2") (pintype "passive"))
      (node (ref "R30") (pin "2") (pinfunction "2_2") (pintype "passive"))
      (node (ref "R4") (pin "2") (pinfunction "2_2") (pintype "passive"))
      (node (ref "R40") (pin "2") (pinfunction "2_2") (pintype "passive"))
      (node (ref "R50") (pin "2") (pinfunction "2_2") (pintype "passive"))
      (node (ref "R60") (pin "2") (pinfunction "2_2") (pintype "passive"))
    )
    (net (code "225") (name "unconnected-(IC8A-QH*-Pad9)") (class "Default")
      (node (ref "IC8") (pin "9") (pinfunction "QH*_9") (pintype "tri_state"))
    )
    (net (code "226") (name "unconnected-(N2-DP-PadKDP)") (class "Default")
      (node (ref "N2") (pin "KDP") (pinfunction "DP_KDP") (pintype "bidirectional"))
    )
    (net (code "227") (name "unconnected-(N3-DP-PadKDP)") (class "Default")
      (node (ref "N3") (pin "KDP") (pinfunction "DP_KDP") (pintype "bidirectional"))
    )
    (net (code "228") (name "unconnected-(N4-DP-PadKDP)") (class "Default")
      (node (ref "N4") (pin "KDP") (pinfunction "DP_KDP") (pintype "bidirectional"))
    )
    (net (code "229") (name "unconnected-(N5-DP-PadKDP)") (class "Default")
      (node (ref "N5") (pin "KDP") (pinfunction "DP_KDP") (pintype "bidirectional"))
    )
    (net (code "230") (name "unconnected-(N6-DP-PadKDP)") (class "Default")
      (node (ref "N6") (pin "KDP") (pinfunction "DP_KDP") (pintype "bidirectional"))
    )
  )
)
